# ctia_alone.net
KiCad netlist of a schematic drawn in EAGLE
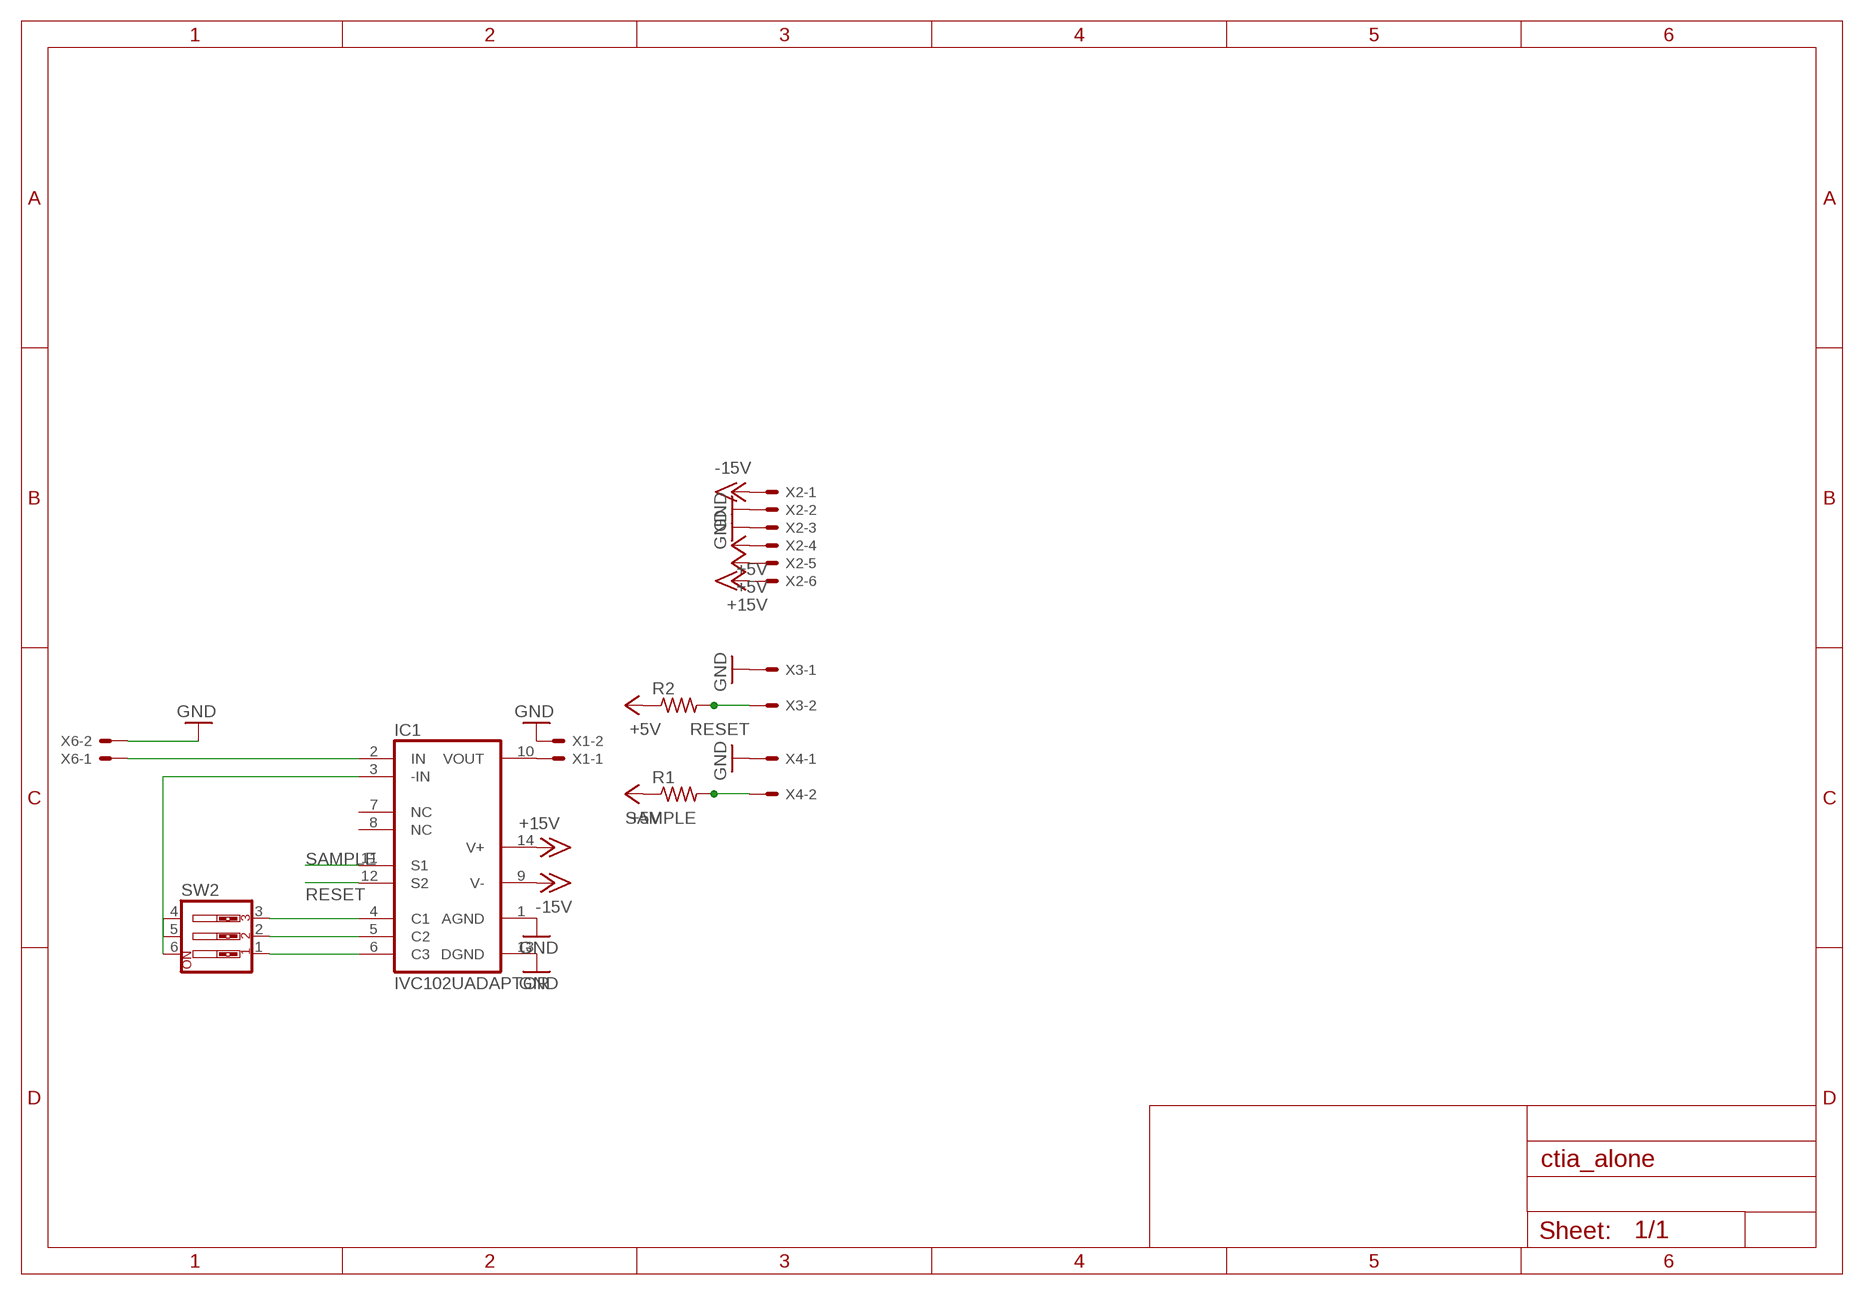
[diagram p0: schematic, sheet 1]

(export (version "E")
  (design (tool "Eeschema 10.0.6"))
  (components
    (comp (ref "IC1")
      (value "IVC102UADAPTOR")
      (footprint "eagle-import:DIL14")
      (libsource (lib "eagle-import") (part "IVC102UADAPTOR"))
    )
    (comp (ref "R1")
      (value "R-US_0207/12")
      (footprint "eagle-import:0207_12")
      (libsource (lib "eagle-import") (part "R-US_0207/12"))
    )
    (comp (ref "R2")
      (value "R-US_0207/10")
      (footprint "eagle-import:0207_10")
      (libsource (lib "eagle-import") (part "R-US_0207/10"))
    )
    (comp (ref "SW2")
      (value "SW_DIP-3")
      (footprint "eagle-import:EDG-03")
      (libsource (lib "eagle-import") (part "SW_DIP-3"))
    )
    (comp (ref "X1")
      (value "KK-156-2")
      (footprint "eagle-import:KK-156-2")
      (libsource (lib "eagle-import") (part "KK-156-2"))
    )
    (comp (ref "X2")
      (value "KK-156-6")
      (footprint "eagle-import:KK-156-6")
      (libsource (lib "eagle-import") (part "KK-156-6"))
    )
    (comp (ref "X3")
      (value "KK-156-2")
      (footprint "eagle-import:KK-156-2")
      (libsource (lib "eagle-import") (part "KK-156-2"))
    )
    (comp (ref "X4")
      (value "KK-156-2")
      (footprint "eagle-import:KK-156-2")
      (libsource (lib "eagle-import") (part "KK-156-2"))
    )
    (comp (ref "X6")
      (value "KK-156-2")
      (footprint "eagle-import:KK-156-2")
      (libsource (lib "eagle-import") (part "KK-156-2"))
    )
  )
  (nets
    (net (code "1") (name "+5V") (class "Default")
      (node (ref "R1") (pin "1") (pinfunction "1_1") (pintype "passive"))
      (node (ref "R2") (pin "1") (pinfunction "1_1") (pintype "passive"))
      (node (ref "X2") (pin "4") (pinfunction "S_4") (pintype "passive"))
      (node (ref "X2") (pin "5") (pinfunction "S_5") (pintype "passive"))
    )
    (net (code "2") (name "+15V") (class "Default")
      (node (ref "IC1") (pin "14") (pinfunction "V+_14") (pintype "power_in"))
      (node (ref "X2") (pin "6") (pinfunction "S_6") (pintype "passive"))
    )
    (net (code "3") (name "-15V") (class "Default")
      (node (ref "IC1") (pin "9") (pinfunction "V-_9") (pintype "power_in"))
      (node (ref "X2") (pin "1") (pinfunction "S_1") (pintype "passive"))
    )
    (net (code "4") (name "/RESET") (class "Default")
      (node (ref "IC1") (pin "12") (pinfunction "S2_12") (pintype "input"))
      (node (ref "R2") (pin "2") (pinfunction "2_2") (pintype "passive"))
      (node (ref "X3") (pin "2") (pinfunction "S_2") (pintype "passive"))
    )
    (net (code "5") (name "/SAMPLE") (class "Default")
      (node (ref "IC1") (pin "11") (pinfunction "S1_11") (pintype "input"))
      (node (ref "R1") (pin "2") (pinfunction "2_2") (pintype "passive"))
      (node (ref "X4") (pin "2") (pinfunction "S_2") (pintype "passive"))
    )
    (net (code "6") (name "GND") (class "Default")
      (node (ref "IC1") (pin "1") (pinfunction "AGND_1") (pintype "power_in"))
      (node (ref "IC1") (pin "13") (pinfunction "DGND_13") (pintype "power_in"))
      (node (ref "X1") (pin "2") (pinfunction "S_2") (pintype "passive"))
      (node (ref "X2") (pin "2") (pinfunction "S_2") (pintype "passive"))
      (node (ref "X2") (pin "3") (pinfunction "S_3") (pintype "passive"))
      (node (ref "X3") (pin "1") (pinfunction "S_1") (pintype "passive"))
      (node (ref "X4") (pin "1") (pinfunction "S_1") (pintype "passive"))
      (node (ref "X6") (pin "2") (pinfunction "S_2") (pintype "passive"))
    )
    (net (code "7") (name "Net-(IC1--IN)") (class "Default")
      (node (ref "IC1") (pin "3") (pinfunction "-IN_3") (pintype "input"))
      (node (ref "SW2") (pin "4") (pinfunction "4_4") (pintype "passive"))
      (node (ref "SW2") (pin "5") (pinfunction "5_5") (pintype "passive"))
      (node (ref "SW2") (pin "6") (pinfunction "6_6") (pintype "passive"))
    )
    (net (code "8") (name "Net-(IC1-C1)") (class "Default")
      (node (ref "IC1") (pin "4") (pinfunction "C1_4") (pintype "passive"))
      (node (ref "SW2") (pin "3") (pinfunction "3_3") (pintype "passive"))
    )
    (net (code "9") (name "Net-(IC1-C2)") (class "Default")
      (node (ref "IC1") (pin "5") (pinfunction "C2_5") (pintype "passive"))
      (node (ref "SW2") (pin "2") (pinfunction "2_2") (pintype "passive"))
    )
    (net (code "10") (name "Net-(IC1-C3)") (class "Default")
      (node (ref "IC1") (pin "6") (pinfunction "C3_6") (pintype "passive"))
      (node (ref "SW2") (pin "1") (pinfunction "1_1") (pintype "passive"))
    )
    (net (code "11") (name "Net-(IC1-IN)") (class "Default")
      (node (ref "IC1") (pin "2") (pinfunction "IN_2") (pintype "input"))
      (node (ref "X6") (pin "1") (pinfunction "S_1") (pintype "passive"))
    )
    (net (code "12") (name "Net-(IC1-VOUT)") (class "Default")
      (node (ref "IC1") (pin "10") (pinfunction "VOUT_10") (pintype "output"))
      (node (ref "X1") (pin "1") (pinfunction "S_1") (pintype "passive"))
    )
    (net (code "13") (name "unconnected-(IC1-NC-Pad7)") (class "Default")
      (node (ref "IC1") (pin "7") (pinfunction "NC_7") (pintype "no_connect"))
    )
    (net (code "14") (name "unconnected-(IC1-NC-Pad8)") (class "Default")
      (node (ref "IC1") (pin "8") (pinfunction "NC_8") (pintype "no_connect"))
    )
  )
)
